# bender_isometer_interface.net
KiCad netlist of a schematic drawn in Altium Designer
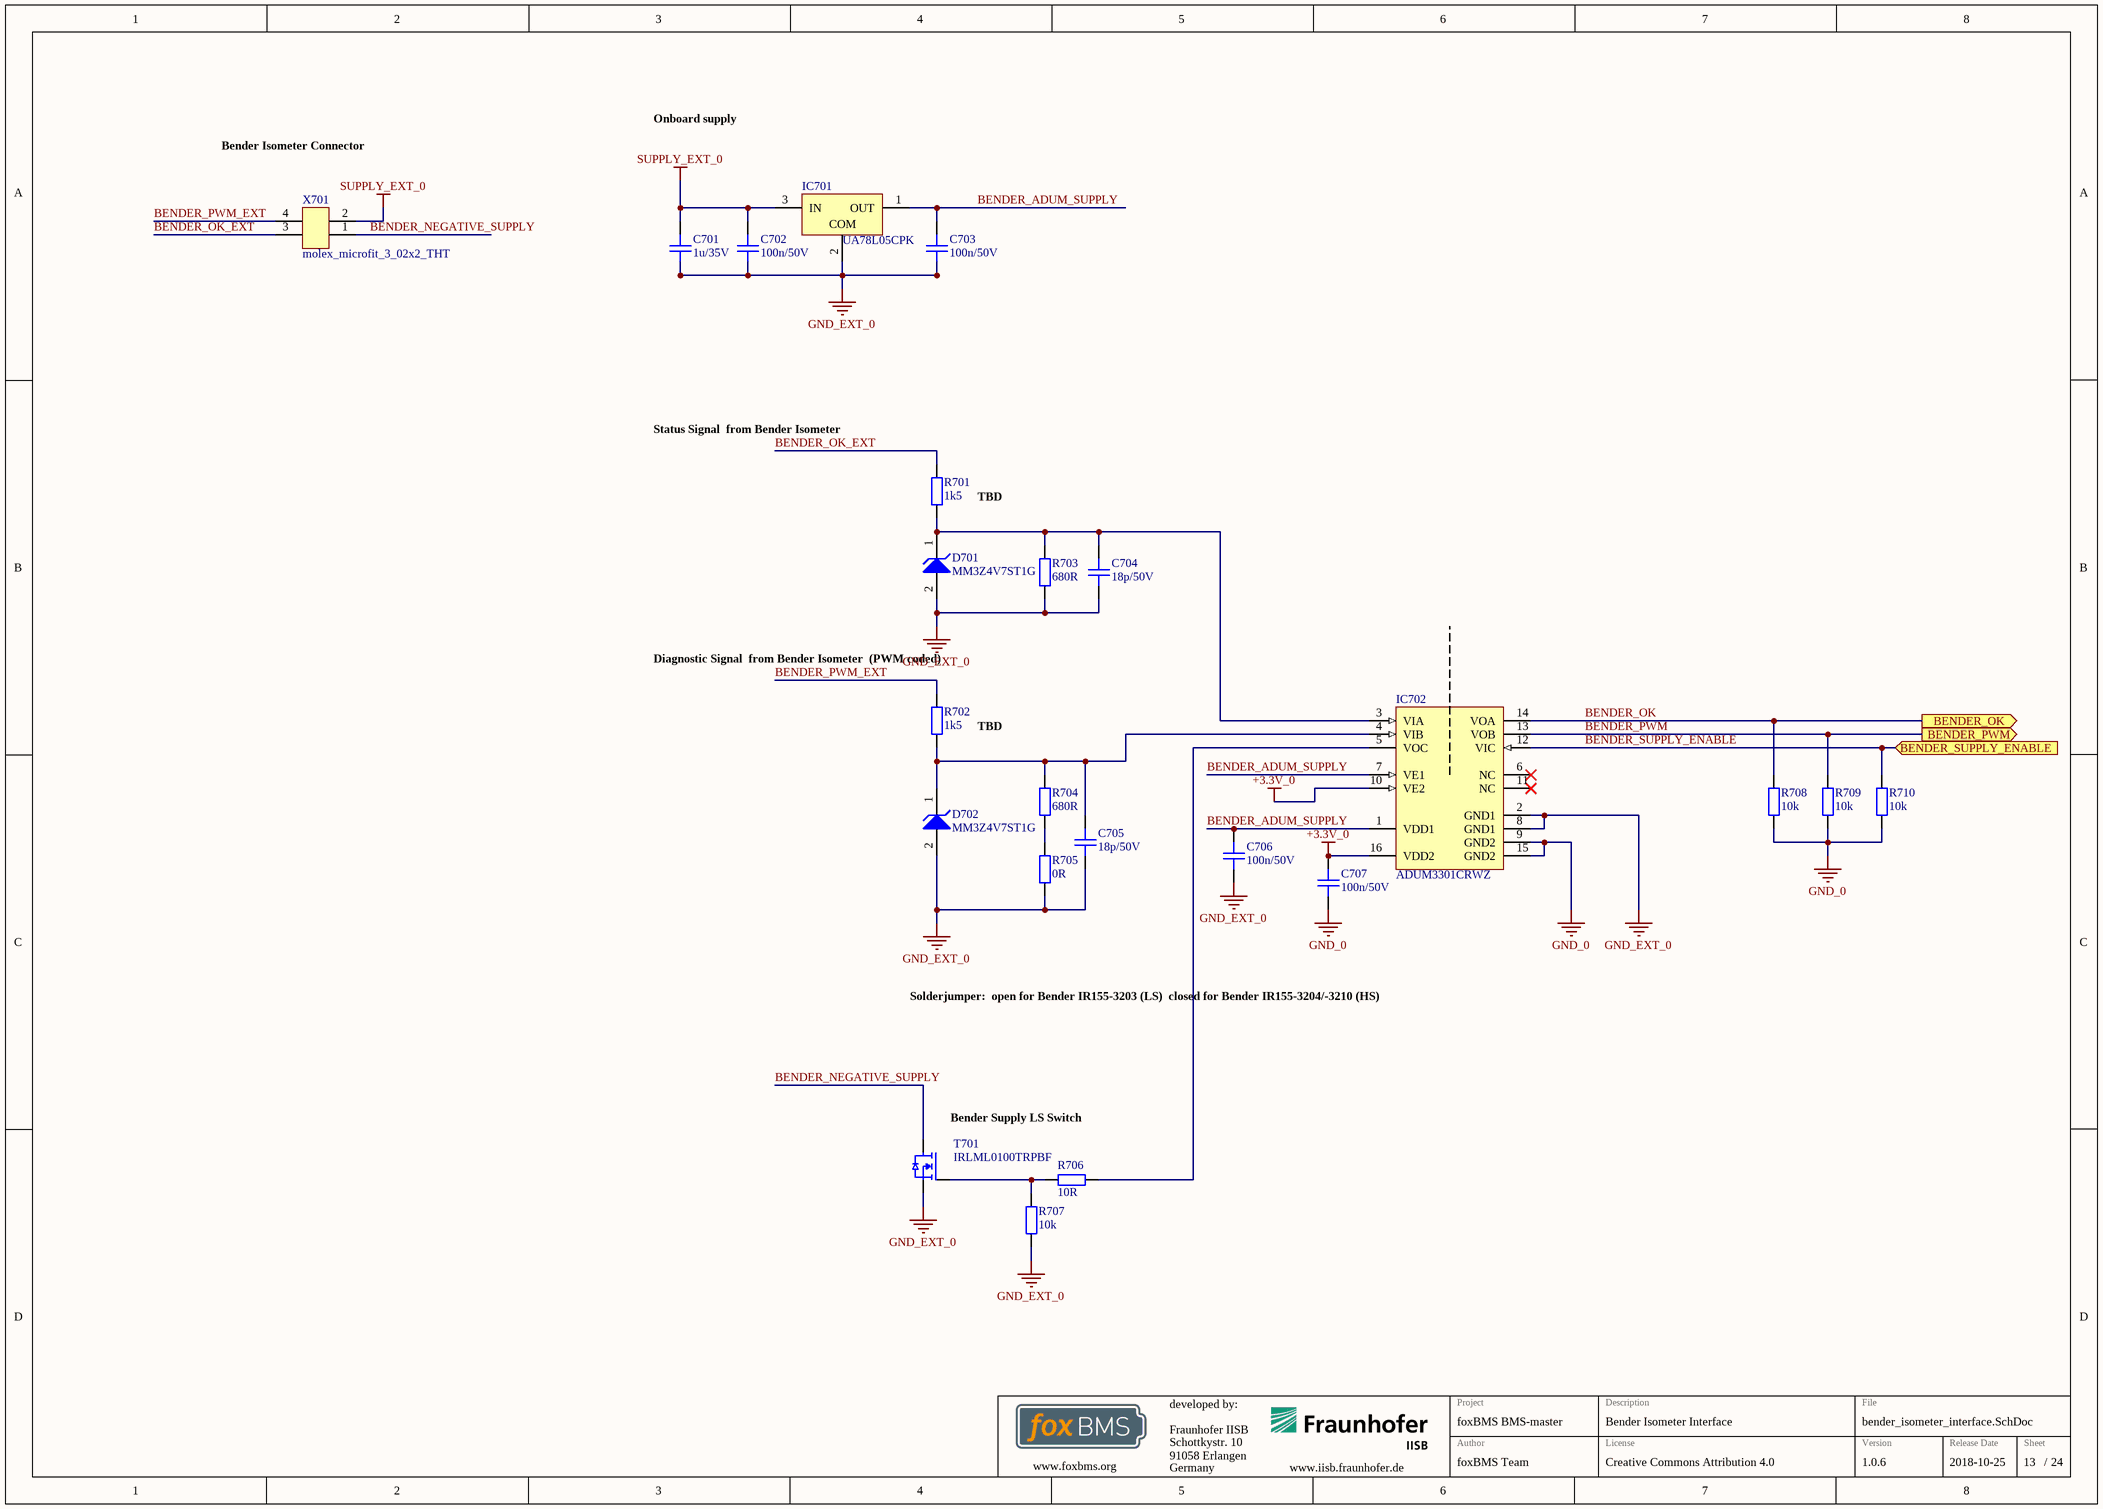
[diagram p0: bender_isometer_interface.SchDoc]

(export (version "E")
  (design (tool "Eeschema 10.0.6"))
  (components
    (comp (ref "C701")
      (value "1u/35V")
      (footprint "CAPC1608X08N")
      (description "MLCC")
      (fields (field (name "PART NUMBER") "gen_C_ceramic_1u_35V_X7R_0603"))
      (libsource (lib "OE750") (part "C"))
    )
    (comp (ref "C702")
      (value "100n/50V")
      (footprint "CAPC1608X08N")
      (description "MLCC")
      (fields (field (name "PART NUMBER") "gen_C_ceramic_100n_50V_X7R_0603"))
      (libsource (lib "OE750") (part "C"))
    )
    (comp (ref "C703")
      (value "100n/50V")
      (footprint "CAPC1608X08N")
      (description "MLCC")
      (fields (field (name "PART NUMBER") "gen_C_ceramic_100n_50V_X7R_0603"))
      (libsource (lib "OE750") (part "C"))
    )
    (comp (ref "C704")
      (value "18p/50V")
      (footprint "CAPC1608X08N")
      (description "MLCC")
      (fields (field (name "PART NUMBER") "gen_C_ceramic_18p_50V_C0G_0603"))
      (libsource (lib "OE750") (part "C"))
    )
    (comp (ref "C705")
      (value "18p/50V")
      (footprint "CAPC1608X08N")
      (description "MLCC")
      (fields (field (name "PART NUMBER") "gen_C_ceramic_18p_50V_C0G_0603"))
      (libsource (lib "OE750") (part "C"))
    )
    (comp (ref "C706")
      (value "100n/50V")
      (footprint "CAPC1608X08N")
      (description "MLCC")
      (fields (field (name "PART NUMBER") "gen_C_ceramic_100n_50V_X7R_0603"))
      (libsource (lib "OE750") (part "C"))
    )
    (comp (ref "C707")
      (value "100n/50V")
      (footprint "CAPC1608X08N")
      (description "MLCC")
      (fields (field (name "PART NUMBER") "gen_C_ceramic_100n_50V_X7R_0603"))
      (libsource (lib "OE750") (part "C"))
    )
    (comp (ref "D701")
      (value "MM3Z4V7ST1G")
      (footprint "ONSC-SOD-323-2-477-02_V")
      (description "Zener Voltage Regulator, 300 mW, Tight Tolerance Portfolio, 2-Pin SOD-323, Pb-Free, Tape and Reel")
      (fields (field (name "MANUFACTURER") "On Semiconductor"))
      (libsource (lib "Altium Content Vault") (part "ONSC-K1A2-2"))
    )
    (comp (ref "D702")
      (value "MM3Z4V7ST1G")
      (footprint "ONSC-SOD-323-2-477-02_V")
      (description "Zener Voltage Regulator, 300 mW, Tight Tolerance Portfolio, 2-Pin SOD-323, Pb-Free, Tape and Reel")
      (fields (field (name "MANUFACTURER") "On Semiconductor"))
      (libsource (lib "Altium Content Vault") (part "ONSC-K1A2-2"))
    )
    (comp (ref "IC701")
      (value "UA78L05CPK")
      (footprint "PK0003A_L")
      (fields (field (name "MANUFACTURER") "TexasInstruments"))
      (libsource (lib "Altium Content Vault") (part "TI-UA78L05-PK-3"))
    )
    (comp (ref "IC702")
      (value "ADUM3301CRWZ")
      (footprint "ADI-RW-16_N")
      (fields (field (name "MANUFACTURER") "Analog Devices"))
      (libsource (lib "Altium Content Vault") (part "ADI-ADUMX301-RW-16"))
    )
    (comp (ref "R701")
      (value "1k5")
      (footprint "RESC1608X05N")
      (description "SMD Resistor 1k5 0603")
      (fields (field (name "PART NUMBER") "gen_R_1k5_0603") (field (name "TOLERANCE") "1%"))
      (libsource (lib "OE750") (part "R"))
    )
    (comp (ref "R702")
      (value "1k5")
      (footprint "RESC1608X05N")
      (description "SMD Resistor 1k5 0603")
      (fields (field (name "PART NUMBER") "gen_R_1k5_0603") (field (name "TOLERANCE") "1%"))
      (libsource (lib "OE750") (part "R"))
    )
    (comp (ref "R703")
      (value "680R")
      (footprint "RESC1608X05N")
      (description "SMD Resistor 680R 0603")
      (fields (field (name "PART NUMBER") "gen_R_680R_0603") (field (name "TOLERANCE") "1%"))
      (libsource (lib "OE750") (part "R"))
    )
    (comp (ref "R704")
      (value "680R")
      (footprint "RESC1608X05N")
      (description "SMD Resistor 680R 0603")
      (fields (field (name "PART NUMBER") "gen_R_680R_0603") (field (name "TOLERANCE") "1%"))
      (libsource (lib "OE750") (part "R"))
    )
    (comp (ref "R705")
      (value "0R")
      (footprint "RESC1608X05N")
      (description "SMD Resistor 0R 0603")
      (fields (field (name "PART NUMBER") "gen_R_0R_0603") (field (name "POWER") "0.1W"))
      (libsource (lib "OE750") (part "R"))
    )
    (comp (ref "R706")
      (value "10R")
      (footprint "RESC1608X05N")
      (description "SMD Resistor 10R 0603")
      (fields (field (name "PART NUMBER") "gen_R_10R_0603") (field (name "TOLERANCE") "1%"))
      (libsource (lib "OE750") (part "R"))
    )
    (comp (ref "R707")
      (value "10k")
      (footprint "RESC1608X05N")
      (description "SMD Resistor 10k 0603")
      (fields (field (name "PART NUMBER") "gen_R_10k_0603") (field (name "TOLERANCE") "1%"))
      (libsource (lib "OE750") (part "R"))
    )
    (comp (ref "R708")
      (value "10k")
      (footprint "RESC1608X05N")
      (description "SMD Resistor 10k 0603")
      (fields (field (name "PART NUMBER") "gen_R_10k_0603") (field (name "TOLERANCE") "1%"))
      (libsource (lib "OE750") (part "R"))
    )
    (comp (ref "R709")
      (value "10k")
      (footprint "RESC1608X05N")
      (description "SMD Resistor 10k 0603")
      (fields (field (name "PART NUMBER") "gen_R_10k_0603") (field (name "TOLERANCE") "1%"))
      (libsource (lib "OE750") (part "R"))
    )
    (comp (ref "R710")
      (value "10k")
      (footprint "RESC1608X05N")
      (description "SMD Resistor 10k 0603")
      (fields (field (name "PART NUMBER") "gen_R_10k_0603") (field (name "TOLERANCE") "1%"))
      (libsource (lib "OE750") (part "R"))
    )
    (comp (ref "T701")
      (value "IRLML0100TRPBF")
      (footprint "SOT95P237X110-3N")
      (description "MOSFET-Transistor, n-Kanal, 1.6 A, 100 V, 0.178 ohm, 10 V, 2.5 V")
      (fields (field (name "MANUFACTURER") "Infineon"))
      (libsource (lib "OE750") (part "NMOS"))
    )
    (comp (ref "X701")
      (value "molex_microfit_3_02x2_THT")
      (footprint "MOLEX_MICROFIT_02x2_THT")
      (fields (field (name "MANUFACTURER") "Molex"))
      (libsource (lib "OE750") (part "X2x2"))
    )
  )
  (nets
    (net (code "1") (name "+3.3V_0") (class "Default")
      (node (ref "C707") (pin "1") (pinfunction "1_1") (pintype "passive"))
      (node (ref "IC702") (pin "10") (pinfunction "VE2_10") (pintype "input"))
      (node (ref "IC702") (pin "16") (pinfunction "VDD2_16") (pintype "power_in"))
    )
    (net (code "2") (name "/BENDER_ADUM_SUPPLY") (class "Default")
      (node (ref "C703") (pin "1") (pinfunction "1_1") (pintype "passive"))
      (node (ref "C706") (pin "1") (pinfunction "1_1") (pintype "passive"))
      (node (ref "IC701") (pin "1") (pinfunction "OUT_1") (pintype "power_in"))
      (node (ref "IC702") (pin "1") (pinfunction "VDD1_1") (pintype "power_in"))
      (node (ref "IC702") (pin "7") (pinfunction "VE1_7") (pintype "input"))
    )
    (net (code "3") (name "/BENDER_NEGATIVE_SUPPLY") (class "Default")
      (node (ref "T701") (pin "D") (pinfunction "D_D") (pintype "passive"))
      (node (ref "X701") (pin "1") (pintype "passive"))
    )
    (net (code "4") (name "/BENDER_OK") (class "Default")
      (node (ref "IC702") (pin "14") (pinfunction "VOA_14") (pintype "tri_state"))
      (node (ref "R708") (pin "2") (pinfunction "2_2") (pintype "passive"))
    )
    (net (code "5") (name "/BENDER_OK_EXT") (class "Default")
      (node (ref "R701") (pin "2") (pinfunction "2_2") (pintype "passive"))
      (node (ref "X701") (pin "3") (pintype "passive"))
    )
    (net (code "6") (name "/BENDER_PWM") (class "Default")
      (node (ref "IC702") (pin "13") (pinfunction "VOB_13") (pintype "tri_state"))
      (node (ref "R709") (pin "2") (pinfunction "2_2") (pintype "passive"))
    )
    (net (code "7") (name "/BENDER_PWM_EXT") (class "Default")
      (node (ref "R702") (pin "2") (pinfunction "2_2") (pintype "passive"))
      (node (ref "X701") (pin "4") (pintype "passive"))
    )
    (net (code "8") (name "/BENDER_SUPPLY_ENABLE") (class "Default")
      (node (ref "IC702") (pin "12") (pinfunction "VIC_12") (pintype "input"))
      (node (ref "R710") (pin "2") (pinfunction "2_2") (pintype "passive"))
    )
    (net (code "9") (name "GND_0") (class "Default")
      (node (ref "C707") (pin "2") (pinfunction "2_2") (pintype "passive"))
      (node (ref "IC702") (pin "15") (pinfunction "GND2_15") (pintype "power_in"))
      (node (ref "IC702") (pin "9") (pinfunction "GND2_9") (pintype "power_in"))
      (node (ref "R708") (pin "1") (pinfunction "1_1") (pintype "passive"))
      (node (ref "R709") (pin "1") (pinfunction "1_1") (pintype "passive"))
      (node (ref "R710") (pin "1") (pinfunction "1_1") (pintype "passive"))
    )
    (net (code "10") (name "GND_EXT_0") (class "Default")
      (node (ref "C701") (pin "2") (pinfunction "2_2") (pintype "passive"))
      (node (ref "C702") (pin "2") (pinfunction "2_2") (pintype "passive"))
      (node (ref "C703") (pin "2") (pinfunction "2_2") (pintype "passive"))
      (node (ref "C704") (pin "2") (pinfunction "2_2") (pintype "passive"))
      (node (ref "C705") (pin "2") (pinfunction "2_2") (pintype "passive"))
      (node (ref "C706") (pin "2") (pinfunction "2_2") (pintype "passive"))
      (node (ref "D701") (pin "2") (pinfunction "A_2") (pintype "passive"))
      (node (ref "D702") (pin "2") (pinfunction "A_2") (pintype "passive"))
      (node (ref "IC701") (pin "2") (pinfunction "COM_2") (pintype "power_in"))
      (node (ref "IC702") (pin "2") (pinfunction "GND1_2") (pintype "power_in"))
      (node (ref "IC702") (pin "8") (pinfunction "GND1_8") (pintype "power_in"))
      (node (ref "R703") (pin "1") (pinfunction "1_1") (pintype "passive"))
      (node (ref "R705") (pin "1") (pinfunction "1_1") (pintype "passive"))
      (node (ref "R707") (pin "2") (pinfunction "2_2") (pintype "passive"))
      (node (ref "T701") (pin "S") (pinfunction "S_S") (pintype "passive"))
    )
    (net (code "11") (name "Net-(D701-K)") (class "Default")
      (node (ref "C704") (pin "1") (pinfunction "1_1") (pintype "passive"))
      (node (ref "D701") (pin "1") (pinfunction "K_1") (pintype "passive"))
      (node (ref "IC702") (pin "3") (pinfunction "VIA_3") (pintype "input"))
      (node (ref "R701") (pin "1") (pinfunction "1_1") (pintype "passive"))
      (node (ref "R703") (pin "2") (pinfunction "2_2") (pintype "passive"))
    )
    (net (code "12") (name "Net-(D702-K)") (class "Default")
      (node (ref "C705") (pin "1") (pinfunction "1_1") (pintype "passive"))
      (node (ref "D702") (pin "1") (pinfunction "K_1") (pintype "passive"))
      (node (ref "IC702") (pin "4") (pinfunction "VIB_4") (pintype "input"))
      (node (ref "R702") (pin "1") (pinfunction "1_1") (pintype "passive"))
      (node (ref "R704") (pin "2") (pinfunction "2_2") (pintype "passive"))
    )
    (net (code "13") (name "Net-(IC702-VOC)") (class "Default")
      (node (ref "IC702") (pin "5") (pinfunction "VOC_5") (pintype "tri_state"))
      (node (ref "R706") (pin "1") (pinfunction "1_1") (pintype "passive"))
    )
    (net (code "14") (name "Net-(R704-Pad1)") (class "Default")
      (node (ref "R704") (pin "1") (pinfunction "1_1") (pintype "passive"))
      (node (ref "R705") (pin "2") (pinfunction "2_2") (pintype "passive"))
    )
    (net (code "15") (name "Net-(R706-Pad2)") (class "Default")
      (node (ref "R706") (pin "2") (pinfunction "2_2") (pintype "passive"))
      (node (ref "R707") (pin "1") (pinfunction "1_1") (pintype "passive"))
      (node (ref "T701") (pin "G") (pinfunction "G_G") (pintype "passive"))
    )
    (net (code "16") (name "SUPPLY_EXT_0") (class "Default")
      (node (ref "C701") (pin "1") (pinfunction "1_1") (pintype "passive"))
      (node (ref "C702") (pin "1") (pinfunction "1_1") (pintype "passive"))
      (node (ref "IC701") (pin "3") (pinfunction "IN_3") (pintype "power_in"))
      (node (ref "X701") (pin "2") (pintype "passive"))
    )
    (net (code "17") (name "unconnected-(IC702-NC-Pad6)") (class "Default")
      (node (ref "IC702") (pin "6") (pinfunction "NC_6") (pintype "passive+no_connect"))
    )
    (net (code "18") (name "unconnected-(IC702-NC-Pad11)") (class "Default")
      (node (ref "IC702") (pin "11") (pinfunction "NC_11") (pintype "passive+no_connect"))
    )
  )
)
